# new_power_management.net
KiCad netlist of a schematic drawn in Altium Designer
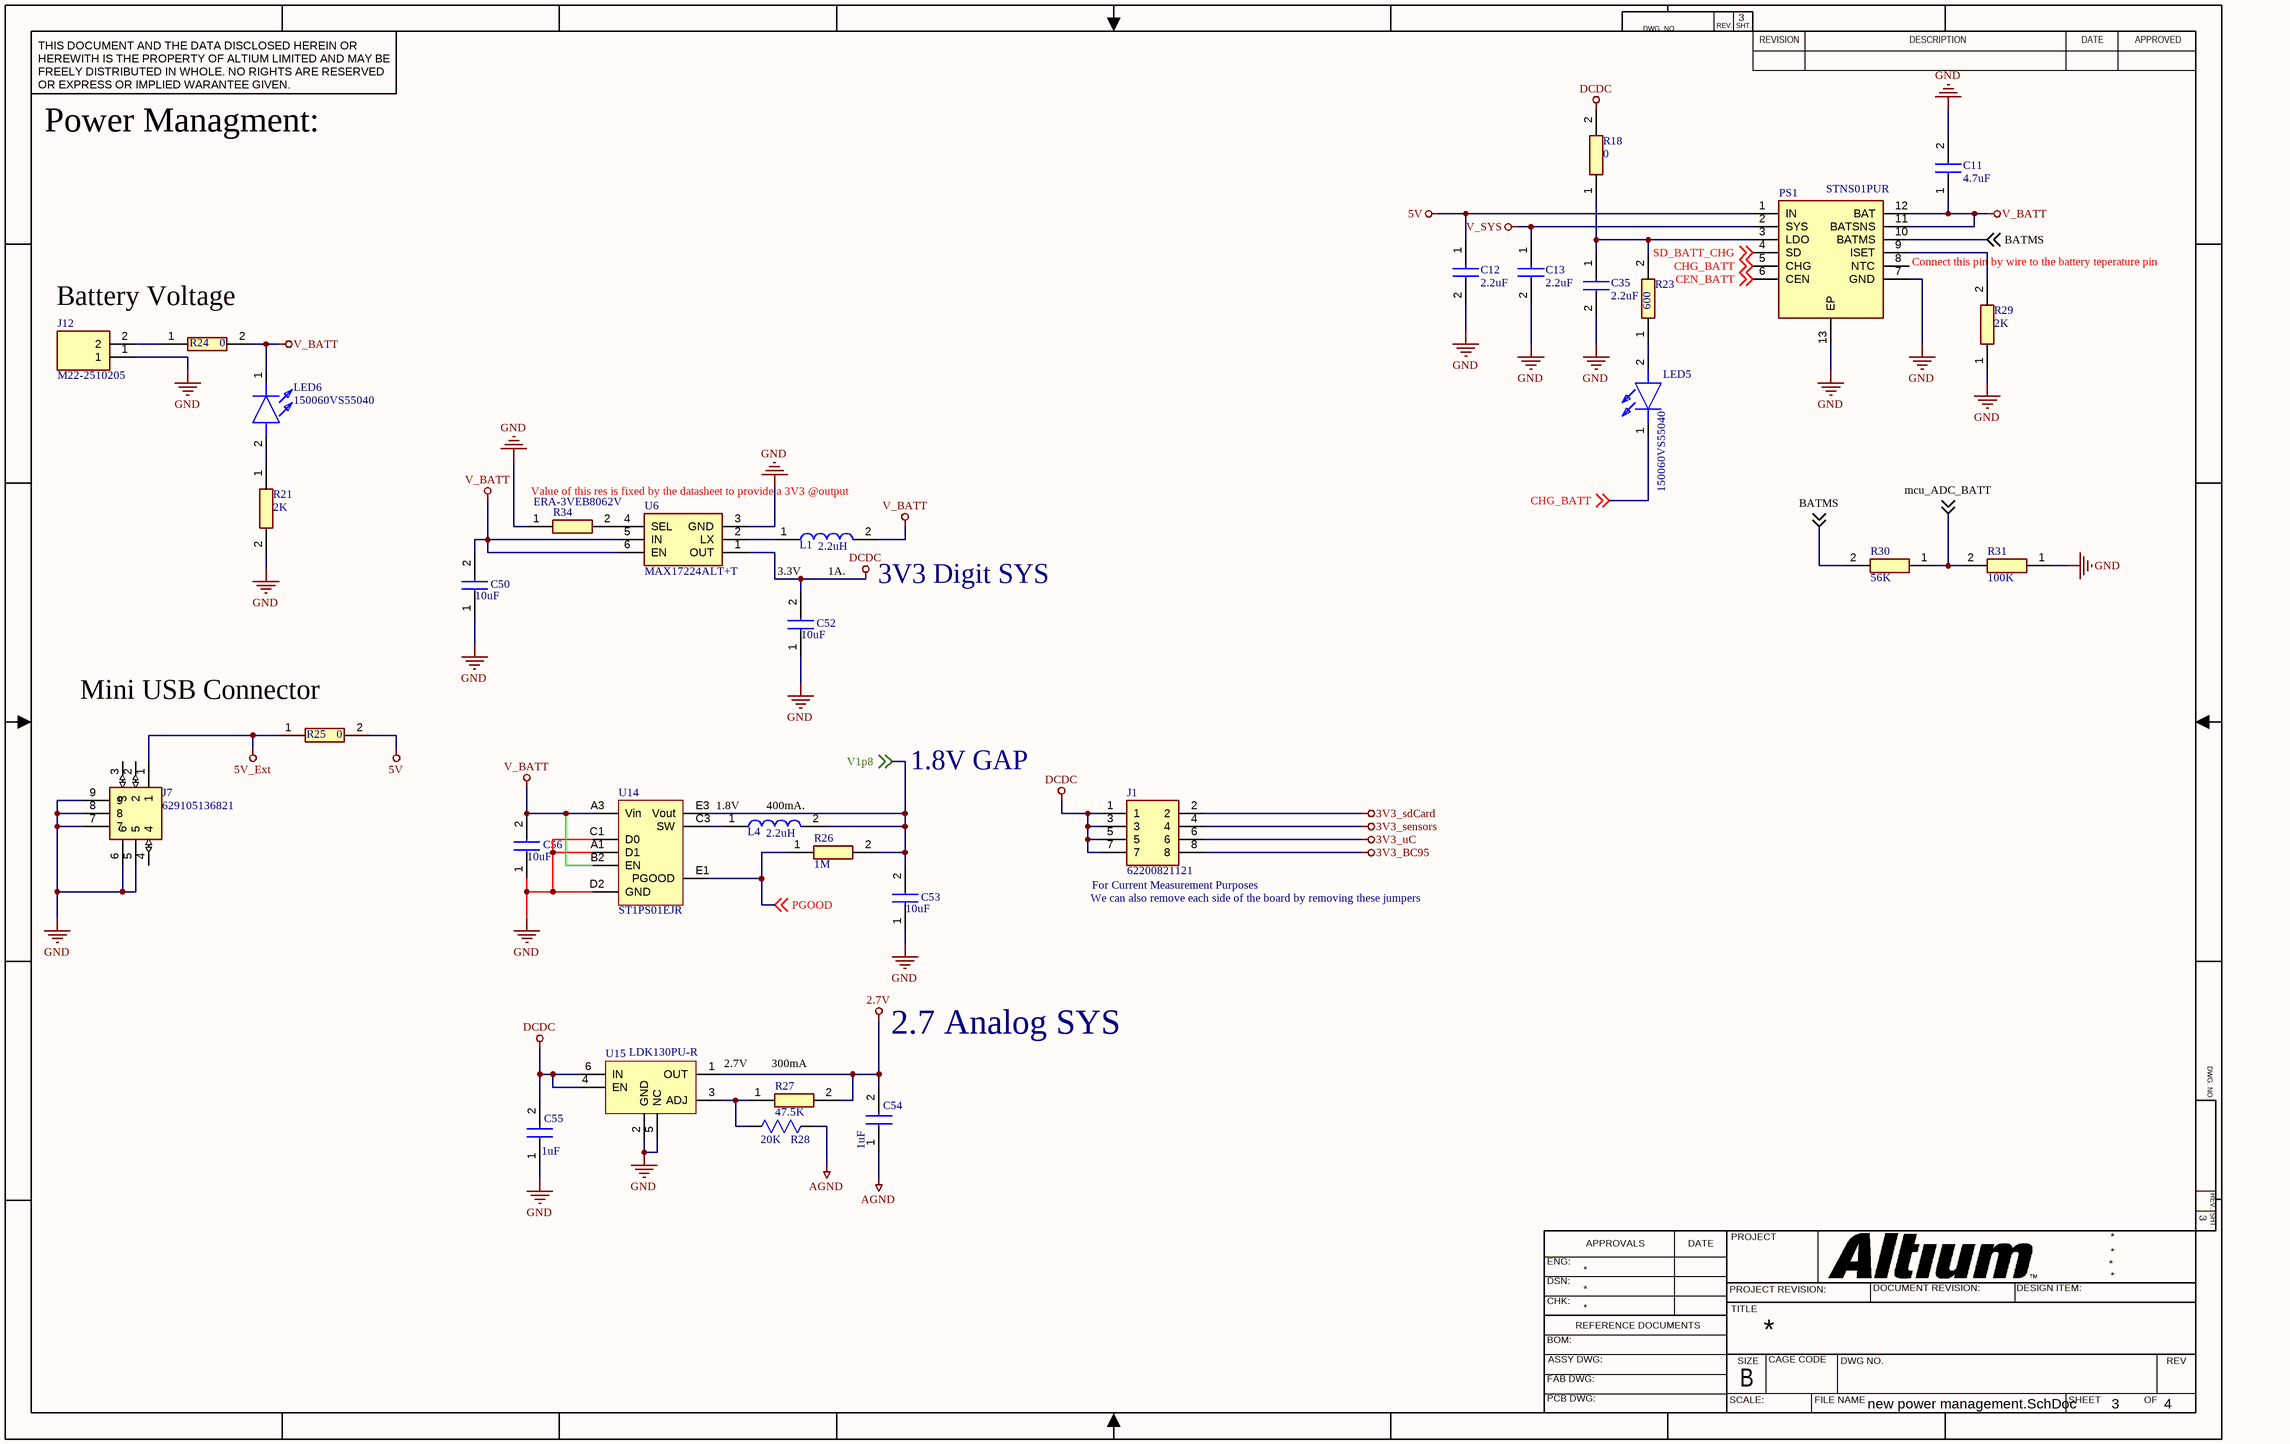
[diagram p0: new power management.SchDoc]

(export (version "E")
  (design (tool "Eeschema 10.0.6"))
  (components
    (comp (ref "C11")
      (value "4.7uF")
      (footprint "SamacSys:CAPC1608X90N")
      (description "Capacitor")
      (fields (field (name "MANUFACTURER_PART_NUMBER") "LMK107BJ475KA-T"))
      (libsource (lib "*") (part "LMK107BJ475KA-T"))
    )
    (comp (ref "C12")
      (value "2.2uF")
      (footprint "SamacSys:CAPC1608X90N")
      (description "Capacitor")
      (fields (field (name "MANUFACTURER_PART_NUMBER") "GRM188R71A225KE15D"))
      (libsource (lib "*") (part "GRM188R71A225KE15D"))
    )
    (comp (ref "C13")
      (value "2.2uF")
      (footprint "SamacSys:CAPC1608X90N")
      (description "Capacitor")
      (fields (field (name "MANUFACTURER_PART_NUMBER") "GRM188R71A225KE15D"))
      (libsource (lib "*") (part "GRM188R71A225KE15D"))
    )
    (comp (ref "C35")
      (value "2.2uF")
      (footprint "SamacSys:CAPC1608X90N")
      (description "Capacitor")
      (fields (field (name "MANUFACTURER_PART_NUMBER") "GRM188R71A225KE15D"))
      (libsource (lib "*") (part "GRM188R71A225KE15D"))
    )
    (comp (ref "C50")
      (value "10uF")
      (footprint "CAPC1005X90N")
      (description "Capacitor")
      (fields (field (name "MANUFACTURER_PART_NUMBER") "CL05A106MP8NUB8"))
      (libsource (lib "*") (part "CL05A106MP8NUB8"))
    )
    (comp (ref "C52")
      (value "10uF")
      (footprint "CAPC1005X90N")
      (description "Capacitor")
      (fields (field (name "MANUFACTURER_PART_NUMBER") "CL05A106MP8NUB8"))
      (libsource (lib "*") (part "CL05A106MP8NUB8"))
    )
    (comp (ref "C53")
      (value "10uF")
      (footprint "CAPC1005X90N")
      (description "Capacitor")
      (fields (field (name "MANUFACTURER_PART_NUMBER") "CL05A106MP8NUB8"))
      (libsource (lib "*") (part "CL05A106MP8NUB8"))
    )
    (comp (ref "C54")
      (value "1uF")
      (footprint "CAPC1005X55N")
      (description "Capacitor")
      (fields (field (name "MANUFACTURER_PART_NUMBER") "JMK105BJ105KV-F"))
      (libsource (lib "SamacSys") (part "JMK105BJ105KV-F"))
    )
    (comp (ref "C55")
      (value "1uF")
      (footprint "CAPC1005X55N")
      (description "Capacitor")
      (fields (field (name "MANUFACTURER_PART_NUMBER") "JMK105BJ105KV-F"))
      (libsource (lib "SamacSys") (part "JMK105BJ105KV-F"))
    )
    (comp (ref "C56")
      (value "10uF")
      (footprint "CAPC1005X90N")
      (description "Capacitor")
      (fields (field (name "MANUFACTURER_PART_NUMBER") "CL05A106MP8NUB8"))
      (libsource (lib "*") (part "CL05A106MP8NUB8"))
    )
    (comp (ref "J1")
      (value "62200821121")
      (footprint "SamacSys:HDRV8W50P127_2X4_508X340X530P")
      (description "Connector")
      (libsource (lib "*") (part "62200821121"))
    )
    (comp (ref "J7")
      (value "629105136821")
      (footprint "MICRO-USB(2.0-SMT-TYPE-B)")
      (description "Connector")
      (fields (field (name "MOUSER2 PART NUMBER") "710-629105136821"))
      (libsource (lib "TemplateNordicSensorNode") (part "629105136821"))
    )
    (comp (ref "J12")
      (value "M22-2510205")
      (footprint "SamacSys:HDRV2W60P0X200_1X2_400X200X525P")
      (description "Connector")
      (libsource (lib "*") (part "M22-2510205"))
    )
    (comp (ref "L1")
      (value "2.2uH")
      (footprint "INDC2520X100N")
      (description "Inductor")
      (fields
        (field (name "MOUSER2 PART NUMBER") "710-74438323022")
        (field (name "MANUFACTURER_PART_NUMBER") "74438323022")
      )
      (libsource (lib "*") (part "74438323022"))
    )
    (comp (ref "L4")
      (value "2.2uH")
      (footprint "INDC2520X100N")
      (description "Inductor")
      (fields
        (field (name "MOUSER2 PART NUMBER") "710-74438323022")
        (field (name "MANUFACTURER_PART_NUMBER") "74438323022")
      )
      (libsource (lib "*") (part "74438323022"))
    )
    (comp (ref "LED5")
      (value "150060VS55040")
      (footprint "SamacSys:LEDM168X50N")
      (description "LED")
      (libsource (lib "*") (part "150060VS55040"))
    )
    (comp (ref "LED6")
      (value "150060VS55040")
      (footprint "LEDM168X50N")
      (description "LED")
      (libsource (lib "*") (part "150060VS55040"))
    )
    (comp (ref "PS1")
      (value "STNS01PUR")
      (footprint "SamacSys:SON45P300X300X80-13N-D")
      (description "Power Supply")
      (libsource (lib "*") (part "STNS01PUR"))
    )
    (comp (ref "R18")
      (value "0")
      (footprint "RESC1608X55N")
      (description "Resistor")
      (fields (field (name "MANUFACTURER_PART_NUMBER") "RC0603FR-070RL"))
      (libsource (lib "*") (part "RC0603FR-070RL"))
    )
    (comp (ref "R21")
      (value "2K")
      (footprint "RESC1005X35N")
      (description "Resistor")
      (fields (field (name "MANUFACTURER_PART_NUMBER") "RT0402FRE072KL"))
      (libsource (lib "*") (part "RT0402FRE072KL"))
    )
    (comp (ref "R23")
      (value "600")
      (footprint "SamacSys:RESC2012X60N")
      (description "Resistor")
      (fields (field (name "MANUFACTURER_PART_NUMBER") "CRCW0805600RFKEAHP"))
      (libsource (lib "*") (part "CRCW0805600RFKEAHP"))
    )
    (comp (ref "R24")
      (value "0")
      (footprint "RESC1608X55N")
      (description "Resistor")
      (fields (field (name "MANUFACTURER_PART_NUMBER") "RC0603FR-070RL"))
      (libsource (lib "") (part "RC0603FR-070RL_1"))
    )
    (comp (ref "R25")
      (value "0")
      (footprint "RESC1608X55N")
      (description "Resistor")
      (fields (field (name "MANUFACTURER_PART_NUMBER") "RC0603FR-070RL"))
      (libsource (lib "") (part "RC0603FR-070RL_1"))
    )
    (comp (ref "R26")
      (value "1M")
      (footprint "RESC1005X40N")
      (description "Resistor")
      (fields (field (name "MANUFACTURER_PART_NUMBER") "CRG0402F1M0"))
      (libsource (lib "*") (part "CRG0402F1M0"))
    )
    (comp (ref "R27")
      (value "47.5K")
      (footprint "RESC1005X40N")
      (description "Resistor")
      (fields
        (field (name "MOUSER2 PART NUMBER") "603-RC0402FR-0747K5L")
        (field (name "MANUFACTURER_PART_NUMBER") "RC0402FR-0747K5L")
      )
      (libsource (lib "*") (part "RC0402FR-0747K5L"))
    )
    (comp (ref "R28")
      (value "20K")
      (footprint "RESC1005X40N")
      (description "20 kOhms Â±1% 0.063W, 1/16W Chip Resistor 0402 _1005 Metric_ Moisture Resistant Thick Film")
      (fields (field (name "MP") "RC0402FR-0720KL") (field (name "MF") "Yageo"))
      (libsource (lib "SnapEDAsch") (part "RC0402FR-0720KL"))
    )
    (comp (ref "R29")
      (value "2K")
      (footprint "SamacSys:RESC1608X55N")
      (description "Resistor")
      (fields (field (name "MANUFACTURER_PART_NUMBER") "CPF0603F2K0C1"))
      (libsource (lib "*") (part "CPF0603F2K0C1"))
    )
    (comp (ref "R30")
      (value "56K")
      (footprint "ERA3KV_(0603)")
      (description "Resistor")
      (fields (field (name "MANUFACTURER_PART_NUMBER") "ERA-3VRW5602V"))
      (libsource (lib "*") (part "ERA-3VRW5602V"))
    )
    (comp (ref "R31")
      (value "100K")
      (footprint "SamacSys:RESC1608X55N")
      (description "Resistor")
      (fields (field (name "MANUFACTURER_PART_NUMBER") "CHV0603AFX-1003ELF"))
      (libsource (lib "*") (part "CHV0603AFX-1003ELF"))
    )
    (comp (ref "R34")
      (value "ERA-3VEB8062V")
      (footprint "SamacSys:ERA3KV_(0603)")
      (description "Resistor")
      (libsource (lib "*") (part "ERA-3VEB8062V"))
    )
    (comp (ref "U6")
      (value "MAX17224ALT+T")
      (footprint "SamacSys:MAX17220ALT")
      (description "Inductor")
      (libsource (lib "*") (part "MAX17224ALT+T"))
    )
    (comp (ref "U14")
      (value "ST1PS01EJR")
      (footprint "ST1PS01EJR")
      (description "400mA Nano-Quiescent Synchronous step-down converter with digital voltage select")
      (fields (field (name "MANUFACTURER") "STMicroelectronics"))
      (libsource (lib "shm_schem_lib") (part "ST1PS01EJR"))
    )
    (comp (ref "U15")
      (value "LDK130PU-R")
      (footprint "SamacSys:LDK130PU18R")
      (description "Adjustable Positive LDO Regulator, 0.8V Min, 5.1V Max, 0.4V Dropout, PDSO6")
      (fields (field (name "MANUFACTURER") "STMicroelectronics") (field (name "TOLERANCE") "2%"))
      (libsource (lib "shm_schem_lib") (part "LDK130PU-R"))
    )
  )
  (nets
    (net (code "1") (name "2.7V") (class "Default")
      (node (ref "C54") (pin "2") (pinfunction "2_2") (pintype "passive"))
      (node (ref "R27") (pin "2") (pinfunction "2_2") (pintype "passive"))
      (node (ref "U15") (pin "1") (pinfunction "OUT_1") (pintype "passive"))
    )
    (net (code "2") (name "3V3_BC95") (class "Default")
      (node (ref "J1") (pin "8") (pinfunction "8_8") (pintype "passive"))
    )
    (net (code "3") (name "3V3_sdCard") (class "Default")
      (node (ref "J1") (pin "2") (pinfunction "2_2") (pintype "passive"))
    )
    (net (code "4") (name "3V3_sensors") (class "Default")
      (node (ref "J1") (pin "4") (pinfunction "4_4") (pintype "passive"))
    )
    (net (code "5") (name "3V3_uC") (class "Default")
      (node (ref "J1") (pin "6") (pinfunction "6_6") (pintype "passive"))
    )
    (net (code "6") (name "5V") (class "Default")
      (node (ref "C12") (pin "1") (pinfunction "1_1") (pintype "passive"))
      (node (ref "PS1") (pin "1") (pinfunction "IN_1") (pintype "passive"))
      (node (ref "R25") (pin "2") (pinfunction "2_2") (pintype "passive"))
    )
    (net (code "7") (name "5V_Ext") (class "Default")
      (node (ref "J7") (pin "1") (pinfunction "1_1") (pintype "passive"))
      (node (ref "R25") (pin "1") (pinfunction "1_1") (pintype "passive"))
    )
    (net (code "8") (name "AGND") (class "Default")
      (node (ref "C54") (pin "1") (pinfunction "1_1") (pintype "passive"))
      (node (ref "R28") (pin "1") (pinfunction "R1_1") (pintype "passive"))
    )
    (net (code "9") (name "BATMS") (class "Default")
      (node (ref "PS1") (pin "10") (pinfunction "BATMS_10") (pintype "passive"))
      (node (ref "R30") (pin "2") (pinfunction "2_2") (pintype "passive"))
    )
    (net (code "10") (name "CEN_BATT") (class "Default")
      (node (ref "PS1") (pin "6") (pinfunction "CEN_6") (pintype "passive"))
    )
    (net (code "11") (name "CHG_BATT") (class "Default")
      (node (ref "LED5") (pin "1") (pinfunction "K_1") (pintype "passive"))
      (node (ref "PS1") (pin "5") (pinfunction "CHG_5") (pintype "passive"))
    )
    (net (code "12") (name "DCDC") (class "Default")
      (node (ref "C52") (pin "2") (pinfunction "2_2") (pintype "passive"))
      (node (ref "C55") (pin "2") (pinfunction "2_2") (pintype "passive"))
      (node (ref "J1") (pin "1") (pinfunction "1_1") (pintype "passive"))
      (node (ref "J1") (pin "3") (pinfunction "3_3") (pintype "passive"))
      (node (ref "J1") (pin "5") (pinfunction "5_5") (pintype "passive"))
      (node (ref "J1") (pin "7") (pinfunction "7_7") (pintype "passive"))
      (node (ref "R18") (pin "2") (pinfunction "2_2") (pintype "passive"))
      (node (ref "U15") (pin "4") (pinfunction "EN_4") (pintype "passive"))
      (node (ref "U15") (pin "6") (pinfunction "IN_6") (pintype "passive"))
      (node (ref "U6") (pin "1") (pinfunction "OUT_1") (pintype "passive"))
    )
    (net (code "13") (name "GND") (class "Default")
      (node (ref "C11") (pin "2") (pinfunction "2_2") (pintype "passive"))
      (node (ref "C12") (pin "2") (pinfunction "2_2") (pintype "passive"))
      (node (ref "C13") (pin "2") (pinfunction "2_2") (pintype "passive"))
      (node (ref "C35") (pin "2") (pinfunction "2_2") (pintype "passive"))
      (node (ref "C50") (pin "1") (pinfunction "1_1") (pintype "passive"))
      (node (ref "C52") (pin "1") (pinfunction "1_1") (pintype "passive"))
      (node (ref "C53") (pin "1") (pinfunction "1_1") (pintype "passive"))
      (node (ref "C55") (pin "1") (pinfunction "1_1") (pintype "passive"))
      (node (ref "C56") (pin "1") (pinfunction "1_1") (pintype "passive"))
      (node (ref "J12") (pin "1") (pinfunction "1_1") (pintype "passive"))
      (node (ref "J7") (pin "5") (pinfunction "5_5") (pintype "passive"))
      (node (ref "J7") (pin "6") (pinfunction "6_6") (pintype "passive"))
      (node (ref "J7") (pin "7") (pinfunction "7_7") (pintype "passive"))
      (node (ref "J7") (pin "8") (pinfunction "8_8") (pintype "passive"))
      (node (ref "J7") (pin "9") (pinfunction "9_9") (pintype "passive"))
      (node (ref "PS1") (pin "13") (pinfunction "EP_13") (pintype "passive"))
      (node (ref "PS1") (pin "7") (pinfunction "GND_7") (pintype "passive"))
      (node (ref "R21") (pin "2") (pinfunction "2_2") (pintype "passive"))
      (node (ref "R29") (pin "1") (pinfunction "1_1") (pintype "passive"))
      (node (ref "R31") (pin "1") (pinfunction "1_1") (pintype "passive"))
      (node (ref "R34") (pin "1") (pinfunction "1_1") (pintype "passive"))
      (node (ref "U14") (pin "A1") (pinfunction "D1_A1") (pintype "passive"))
      (node (ref "U14") (pin "C1") (pinfunction "D0_C1") (pintype "passive"))
      (node (ref "U14") (pin "D2") (pinfunction "GND_D2") (pintype "passive"))
      (node (ref "U15") (pin "2") (pinfunction "GND_2") (pintype "passive"))
      (node (ref "U15") (pin "5") (pinfunction "NC_5") (pintype "passive"))
      (node (ref "U6") (pin "3") (pinfunction "GND_3") (pintype "passive"))
    )
    (net (code "14") (name "Net-(J12-Pad2)") (class "Default")
      (node (ref "J12") (pin "2") (pinfunction "2_2") (pintype "passive"))
      (node (ref "R24") (pin "1") (pinfunction "1_1") (pintype "passive"))
    )
    (net (code "15") (name "Net-(LED5-A)") (class "Default")
      (node (ref "LED5") (pin "2") (pinfunction "A_2") (pintype "passive"))
      (node (ref "R23") (pin "1") (pinfunction "1_1") (pintype "passive"))
    )
    (net (code "16") (name "Net-(LED6-A)") (class "Default")
      (node (ref "LED6") (pin "2") (pinfunction "A_2") (pintype "passive"))
      (node (ref "R21") (pin "1") (pinfunction "1_1") (pintype "passive"))
    )
    (net (code "17") (name "Net-(PS1-ISET)") (class "Default")
      (node (ref "PS1") (pin "9") (pinfunction "ISET_9") (pintype "passive"))
      (node (ref "R29") (pin "2") (pinfunction "2_2") (pintype "passive"))
    )
    (net (code "18") (name "Net-(PS1-LDO)") (class "Default")
      (node (ref "C35") (pin "1") (pinfunction "1_1") (pintype "passive"))
      (node (ref "PS1") (pin "3") (pinfunction "LDO_3") (pintype "passive"))
      (node (ref "R18") (pin "1") (pinfunction "1_1") (pintype "passive"))
      (node (ref "R23") (pin "2") (pinfunction "2_2") (pintype "passive"))
    )
    (net (code "19") (name "Net-(R28-R2)") (class "Default")
      (node (ref "R27") (pin "1") (pinfunction "1_1") (pintype "passive"))
      (node (ref "R28") (pin "2") (pinfunction "R2_2") (pintype "passive"))
      (node (ref "U15") (pin "3") (pinfunction "ADJ_3") (pintype "passive"))
    )
    (net (code "20") (name "Net-(U6-LX)") (class "Default")
      (node (ref "L1") (pin "1") (pinfunction "1_1") (pintype "passive"))
      (node (ref "U6") (pin "2") (pinfunction "LX_2") (pintype "passive"))
    )
    (net (code "21") (name "Net-(U6-SEL)") (class "Default")
      (node (ref "R34") (pin "2") (pinfunction "2_2") (pintype "passive"))
      (node (ref "U6") (pin "4") (pinfunction "SEL_4") (pintype "passive"))
    )
    (net (code "22") (name "Net-(U14-SW)") (class "Default")
      (node (ref "L4") (pin "1") (pinfunction "1_1") (pintype "passive"))
      (node (ref "U14") (pin "C3") (pinfunction "SW_C3") (pintype "passive"))
    )
    (net (code "23") (name "PGOOD") (class "Default")
      (node (ref "R26") (pin "1") (pinfunction "1_1") (pintype "passive"))
      (node (ref "U14") (pin "E1") (pinfunction "PGOOD_E1") (pintype "passive"))
    )
    (net (code "24") (name "SD_BATT_CHG") (class "Default")
      (node (ref "PS1") (pin "4") (pinfunction "SD_4") (pintype "passive"))
    )
    (net (code "25") (name "V1p8") (class "Default")
      (node (ref "C53") (pin "2") (pinfunction "2_2") (pintype "passive"))
      (node (ref "L4") (pin "2") (pinfunction "2_2") (pintype "passive"))
      (node (ref "R26") (pin "2") (pinfunction "2_2") (pintype "passive"))
      (node (ref "U14") (pin "E3") (pinfunction "Vout_E3") (pintype "passive"))
    )
    (net (code "26") (name "V_BATT") (class "Default")
      (node (ref "C11") (pin "1") (pinfunction "1_1") (pintype "passive"))
      (node (ref "C50") (pin "2") (pinfunction "2_2") (pintype "passive"))
      (node (ref "C56") (pin "2") (pinfunction "2_2") (pintype "passive"))
      (node (ref "L1") (pin "2") (pinfunction "2_2") (pintype "passive"))
      (node (ref "LED6") (pin "1") (pinfunction "K_1") (pintype "passive"))
      (node (ref "PS1") (pin "11") (pinfunction "BATSNS_11") (pintype "passive"))
      (node (ref "PS1") (pin "12") (pinfunction "BAT_12") (pintype "passive"))
      (node (ref "R24") (pin "2") (pinfunction "2_2") (pintype "passive"))
      (node (ref "U14") (pin "A3") (pinfunction "Vin_A3") (pintype "passive"))
      (node (ref "U14") (pin "B2") (pinfunction "EN_B2") (pintype "passive"))
      (node (ref "U6") (pin "5") (pinfunction "IN_5") (pintype "passive"))
      (node (ref "U6") (pin "6") (pinfunction "EN_6") (pintype "passive"))
    )
    (net (code "27") (name "V_SYS") (class "Default")
      (node (ref "C13") (pin "1") (pinfunction "1_1") (pintype "passive"))
      (node (ref "PS1") (pin "2") (pinfunction "SYS_2") (pintype "passive"))
    )
    (net (code "28") (name "mcu_ADC_BATT") (class "Default")
      (node (ref "R30") (pin "1") (pinfunction "1_1") (pintype "passive"))
      (node (ref "R31") (pin "2") (pinfunction "2_2") (pintype "passive"))
    )
    (net (code "29") (name "unconnected-(J7-Pad2)") (class "Default")
      (node (ref "J7") (pin "2") (pinfunction "2_2") (pintype "bidirectional"))
    )
    (net (code "30") (name "unconnected-(J7-Pad3)") (class "Default")
      (node (ref "J7") (pin "3") (pinfunction "3_3") (pintype "bidirectional"))
    )
    (net (code "31") (name "unconnected-(J7-Pad4)") (class "Default")
      (node (ref "J7") (pin "4") (pinfunction "4_4") (pintype "bidirectional"))
    )
    (net (code "32") (name "unconnected-(PS1-NTC-Pad8)") (class "Default")
      (node (ref "PS1") (pin "8") (pinfunction "NTC_8") (pintype "passive"))
    )
  )
)
